# MCDU_Board.net
KiCad netlist of a schematic drawn in EAGLE
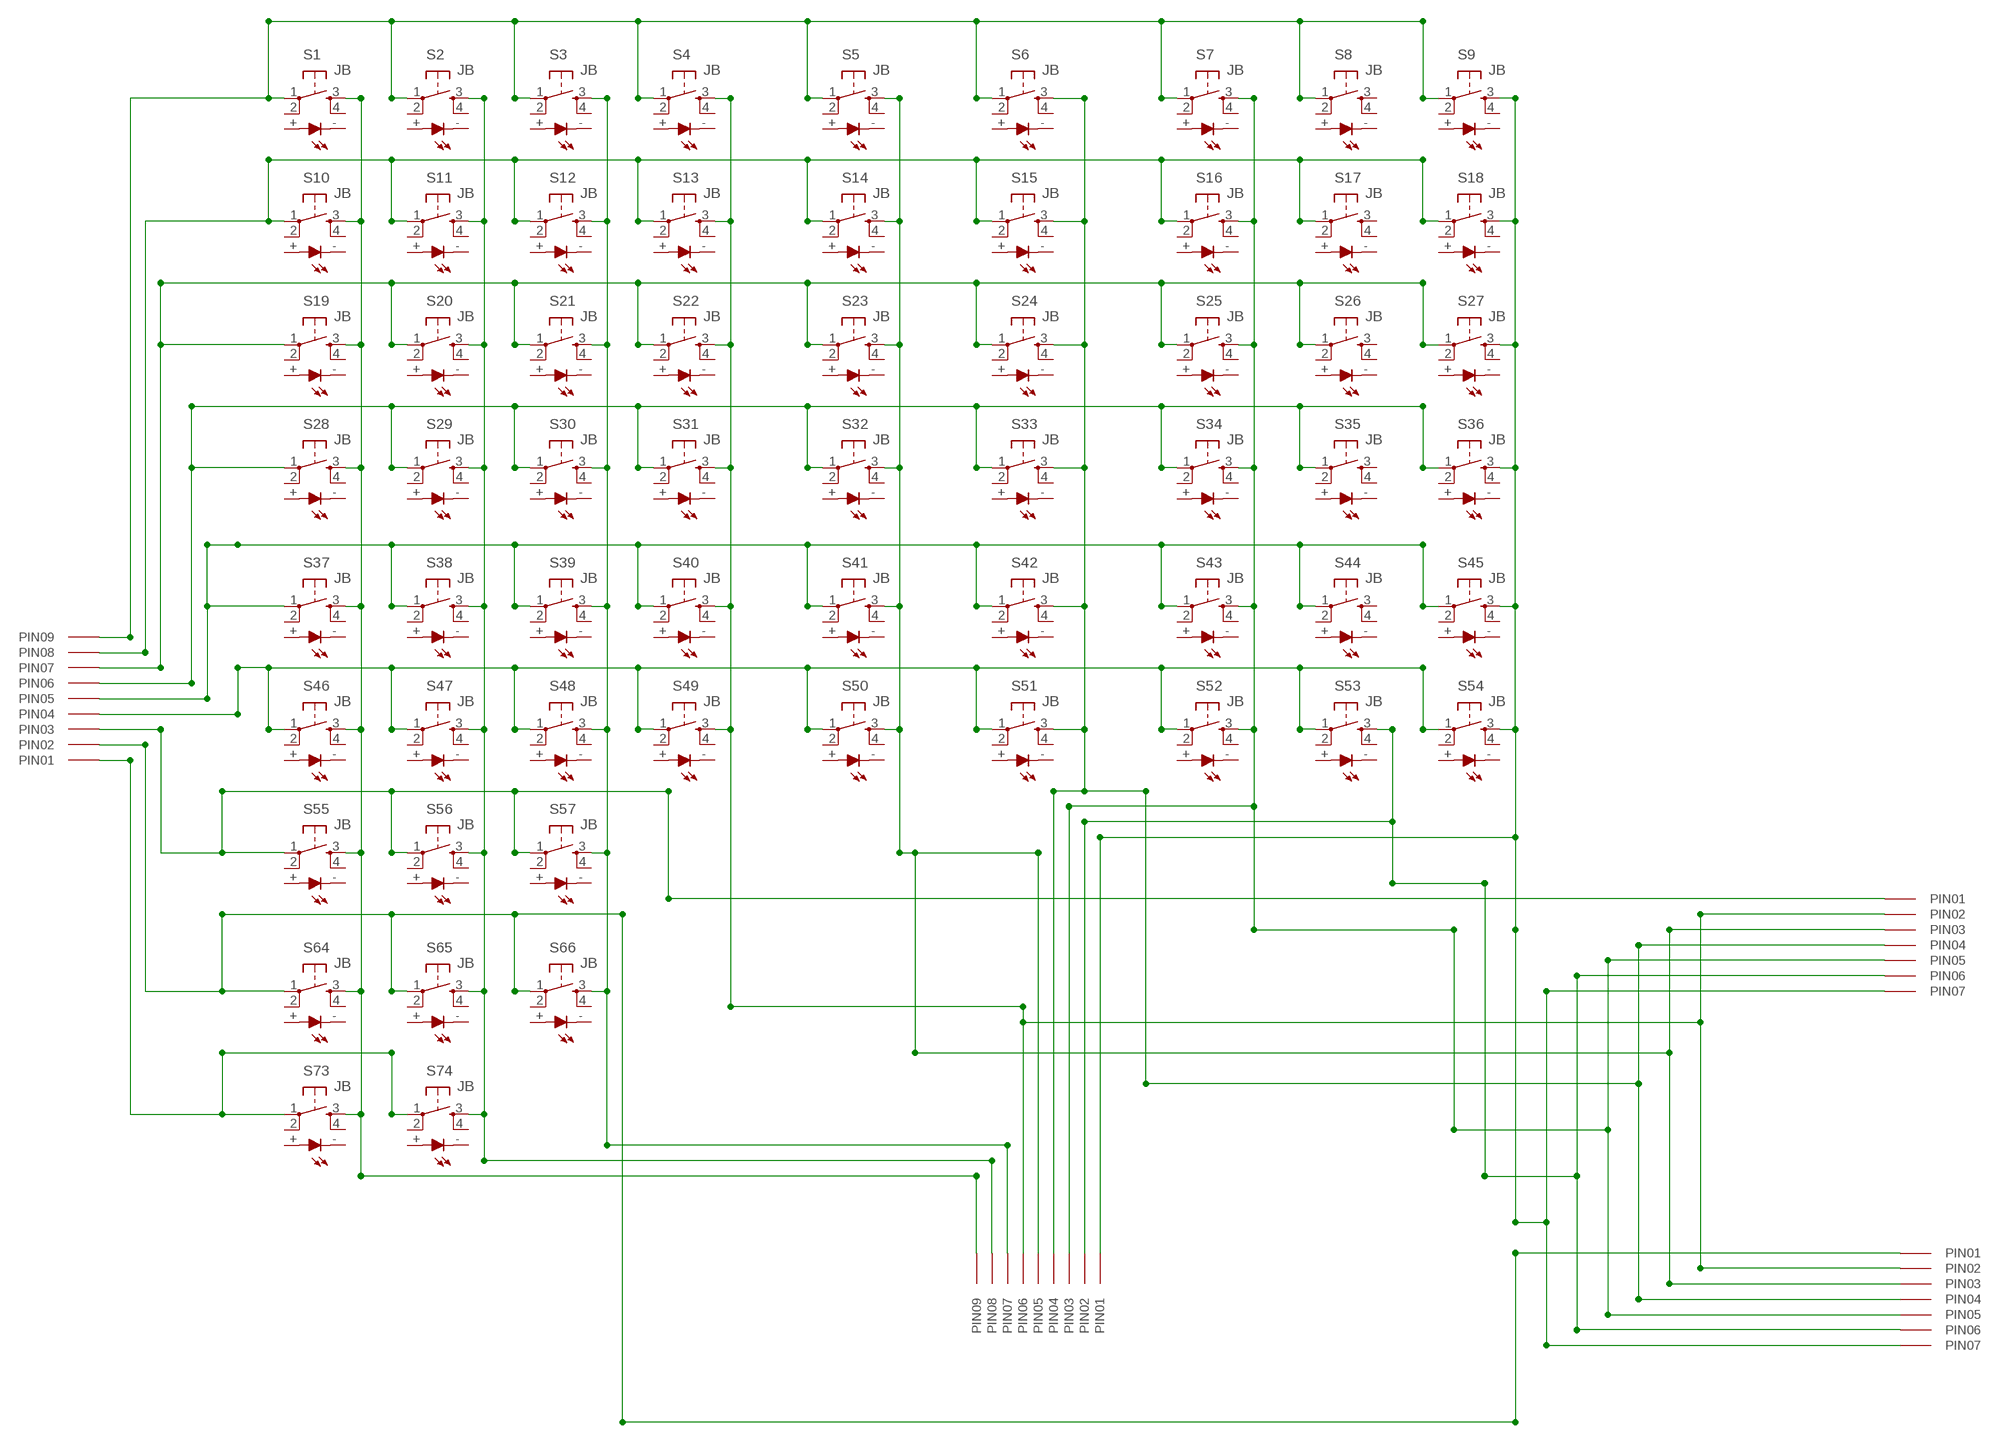
[diagram p0: schematic, sheet 1]

(export (version "E")
  (design (tool "Eeschema 10.0.6"))
  (components
    (comp (ref "S1") (value "JB") (footprint "eagle-import:JB") (libsource (lib "eagle-import") (part "JB")))
    (comp (ref "S2") (value "JB") (footprint "eagle-import:JB") (libsource (lib "eagle-import") (part "JB")))
    (comp (ref "S3") (value "JB") (footprint "eagle-import:JB") (libsource (lib "eagle-import") (part "JB")))
    (comp (ref "S4") (value "JB") (footprint "eagle-import:JB") (libsource (lib "eagle-import") (part "JB")))
    (comp (ref "S5") (value "JB") (footprint "eagle-import:JB") (libsource (lib "eagle-import") (part "JB")))
    (comp (ref "S6") (value "JB") (footprint "eagle-import:JB") (libsource (lib "eagle-import") (part "JB")))
    (comp (ref "S7") (value "JB") (footprint "eagle-import:JB") (libsource (lib "eagle-import") (part "JB")))
    (comp (ref "S8") (value "JB") (footprint "eagle-import:JB") (libsource (lib "eagle-import") (part "JB")))
    (comp (ref "S9") (value "JB") (footprint "eagle-import:JB") (libsource (lib "eagle-import") (part "JB")))
    (comp (ref "S10") (value "JB") (footprint "eagle-import:JB") (libsource (lib "eagle-import") (part "JB")))
    (comp (ref "S11") (value "JB") (footprint "eagle-import:JB") (libsource (lib "eagle-import") (part "JB")))
    (comp (ref "S12") (value "JB") (footprint "eagle-import:JB") (libsource (lib "eagle-import") (part "JB")))
    (comp (ref "S13") (value "JB") (footprint "eagle-import:JB") (libsource (lib "eagle-import") (part "JB")))
    (comp (ref "S14") (value "JB") (footprint "eagle-import:JB") (libsource (lib "eagle-import") (part "JB")))
    (comp (ref "S15") (value "JB") (footprint "eagle-import:JB") (libsource (lib "eagle-import") (part "JB")))
    (comp (ref "S16") (value "JB") (footprint "eagle-import:JB") (libsource (lib "eagle-import") (part "JB")))
    (comp (ref "S17") (value "JB") (footprint "eagle-import:JB") (libsource (lib "eagle-import") (part "JB")))
    (comp (ref "S18") (value "JB") (footprint "eagle-import:JB") (libsource (lib "eagle-import") (part "JB")))
    (comp (ref "S19") (value "JB") (footprint "eagle-import:JB") (libsource (lib "eagle-import") (part "JB")))
    (comp (ref "S20") (value "JB") (footprint "eagle-import:JB") (libsource (lib "eagle-import") (part "JB")))
    (comp (ref "S21") (value "JB") (footprint "eagle-import:JB") (libsource (lib "eagle-import") (part "JB")))
    (comp (ref "S22") (value "JB") (footprint "eagle-import:JB") (libsource (lib "eagle-import") (part "JB")))
    (comp (ref "S23") (value "JB") (footprint "eagle-import:JB") (libsource (lib "eagle-import") (part "JB")))
    (comp (ref "S24") (value "JB") (footprint "eagle-import:JB") (libsource (lib "eagle-import") (part "JB")))
    (comp (ref "S25") (value "JB") (footprint "eagle-import:JB") (libsource (lib "eagle-import") (part "JB")))
    (comp (ref "S26") (value "JB") (footprint "eagle-import:JB") (libsource (lib "eagle-import") (part "JB")))
    (comp (ref "S27") (value "JB") (footprint "eagle-import:JB") (libsource (lib "eagle-import") (part "JB")))
    (comp (ref "S28") (value "JB") (footprint "eagle-import:JB") (libsource (lib "eagle-import") (part "JB")))
    (comp (ref "S29") (value "JB") (footprint "eagle-import:JB") (libsource (lib "eagle-import") (part "JB")))
    (comp (ref "S30") (value "JB") (footprint "eagle-import:JB") (libsource (lib "eagle-import") (part "JB")))
    (comp (ref "S31") (value "JB") (footprint "eagle-import:JB") (libsource (lib "eagle-import") (part "JB")))
    (comp (ref "S32") (value "JB") (footprint "eagle-import:JB") (libsource (lib "eagle-import") (part "JB")))
    (comp (ref "S33") (value "JB") (footprint "eagle-import:JB") (libsource (lib "eagle-import") (part "JB")))
    (comp (ref "S34") (value "JB") (footprint "eagle-import:JB") (libsource (lib "eagle-import") (part "JB")))
    (comp (ref "S35") (value "JB") (footprint "eagle-import:JB") (libsource (lib "eagle-import") (part "JB")))
    (comp (ref "S36") (value "JB") (footprint "eagle-import:JB") (libsource (lib "eagle-import") (part "JB")))
    (comp (ref "S37") (value "JB") (footprint "eagle-import:JB") (libsource (lib "eagle-import") (part "JB")))
    (comp (ref "S38") (value "JB") (footprint "eagle-import:JB") (libsource (lib "eagle-import") (part "JB")))
    (comp (ref "S39") (value "JB") (footprint "eagle-import:JB") (libsource (lib "eagle-import") (part "JB")))
    (comp (ref "S40") (value "JB") (footprint "eagle-import:JB") (libsource (lib "eagle-import") (part "JB")))
    (comp (ref "S41") (value "JB") (footprint "eagle-import:JB") (libsource (lib "eagle-import") (part "JB")))
    (comp (ref "S42") (value "JB") (footprint "eagle-import:JB") (libsource (lib "eagle-import") (part "JB")))
    (comp (ref "S43") (value "JB") (footprint "eagle-import:JB") (libsource (lib "eagle-import") (part "JB")))
    (comp (ref "S44") (value "JB") (footprint "eagle-import:JB") (libsource (lib "eagle-import") (part "JB")))
    (comp (ref "S45") (value "JB") (footprint "eagle-import:JB") (libsource (lib "eagle-import") (part "JB")))
    (comp (ref "S46") (value "JB") (footprint "eagle-import:JB") (libsource (lib "eagle-import") (part "JB")))
    (comp (ref "S47") (value "JB") (footprint "eagle-import:JB") (libsource (lib "eagle-import") (part "JB")))
    (comp (ref "S48") (value "JB") (footprint "eagle-import:JB") (libsource (lib "eagle-import") (part "JB")))
    (comp (ref "S49") (value "JB") (footprint "eagle-import:JB") (libsource (lib "eagle-import") (part "JB")))
    (comp (ref "S50") (value "JB") (footprint "eagle-import:JB") (libsource (lib "eagle-import") (part "JB")))
    (comp (ref "S51") (value "JB") (footprint "eagle-import:JB") (libsource (lib "eagle-import") (part "JB")))
    (comp (ref "S52") (value "JB") (footprint "eagle-import:JB") (libsource (lib "eagle-import") (part "JB")))
    (comp (ref "S53") (value "JB") (footprint "eagle-import:JB") (libsource (lib "eagle-import") (part "JB")))
    (comp (ref "S54") (value "JB") (footprint "eagle-import:JB") (libsource (lib "eagle-import") (part "JB")))
    (comp (ref "S55") (value "JB") (footprint "eagle-import:JB") (libsource (lib "eagle-import") (part "JB")))
    (comp (ref "S56") (value "JB") (footprint "eagle-import:JB") (libsource (lib "eagle-import") (part "JB")))
    (comp (ref "S57") (value "JB") (footprint "eagle-import:JB") (libsource (lib "eagle-import") (part "JB")))
    (comp (ref "S64") (value "JB") (footprint "eagle-import:JB") (libsource (lib "eagle-import") (part "JB")))
    (comp (ref "S65") (value "JB") (footprint "eagle-import:JB") (libsource (lib "eagle-import") (part "JB")))
    (comp (ref "S66") (value "JB") (footprint "eagle-import:JB") (libsource (lib "eagle-import") (part "JB")))
    (comp (ref "S73") (value "JB") (footprint "eagle-import:JB") (libsource (lib "eagle-import") (part "JB")))
    (comp (ref "S74") (value "JB") (footprint "eagle-import:JB") (libsource (lib "eagle-import") (part "JB")))
    (comp (ref "U$1")
      (value "09PINOS")
      (footprint "eagle-import:09PINOS")
      (libsource (lib "eagle-import") (part "09PINOS"))
    )
    (comp (ref "U$2")
      (value "07PINOS")
      (footprint "eagle-import:07PINOS")
      (libsource (lib "eagle-import") (part "07PINOS"))
    )
    (comp (ref "U$3")
      (value "07PINOS")
      (footprint "eagle-import:07PINOS")
      (libsource (lib "eagle-import") (part "07PINOS"))
    )
    (comp (ref "U$4")
      (value "09PINOS")
      (footprint "eagle-import:09PINOS")
      (libsource (lib "eagle-import") (part "09PINOS"))
    )
  )
  (nets
    (net (code "1") (name "Net-(S1-P)") (class "Default")
      (node (ref "S1") (pin "1") (pinfunction "P_1") (pintype "passive"))
      (node (ref "S2") (pin "1") (pinfunction "P_1") (pintype "passive"))
      (node (ref "S3") (pin "1") (pinfunction "P_1") (pintype "passive"))
      (node (ref "S4") (pin "1") (pinfunction "P_1") (pintype "passive"))
      (node (ref "S5") (pin "1") (pinfunction "P_1") (pintype "passive"))
      (node (ref "S6") (pin "1") (pinfunction "P_1") (pintype "passive"))
      (node (ref "S7") (pin "1") (pinfunction "P_1") (pintype "passive"))
      (node (ref "S8") (pin "1") (pinfunction "P_1") (pintype "passive"))
      (node (ref "S9") (pin "1") (pinfunction "P_1") (pintype "passive"))
      (node (ref "U$1") (pin "PIN09") (pinfunction "PIN09_PIN09") (pintype "bidirectional"))
    )
    (net (code "2") (name "Net-(S1-S)") (class "Default")
      (node (ref "S1") (pin "3") (pinfunction "S_3") (pintype "passive"))
      (node (ref "S10") (pin "3") (pinfunction "S_3") (pintype "passive"))
      (node (ref "S19") (pin "3") (pinfunction "S_3") (pintype "passive"))
      (node (ref "S28") (pin "3") (pinfunction "S_3") (pintype "passive"))
      (node (ref "S37") (pin "3") (pinfunction "S_3") (pintype "passive"))
      (node (ref "S46") (pin "3") (pinfunction "S_3") (pintype "passive"))
      (node (ref "S55") (pin "3") (pinfunction "S_3") (pintype "passive"))
      (node (ref "S64") (pin "3") (pinfunction "S_3") (pintype "passive"))
      (node (ref "S73") (pin "3") (pinfunction "S_3") (pintype "passive"))
      (node (ref "U$4") (pin "PIN09") (pinfunction "PIN09_PIN09") (pintype "bidirectional"))
    )
    (net (code "3") (name "Net-(S10-P)") (class "Default")
      (node (ref "S10") (pin "1") (pinfunction "P_1") (pintype "passive"))
      (node (ref "S11") (pin "1") (pinfunction "P_1") (pintype "passive"))
      (node (ref "S12") (pin "1") (pinfunction "P_1") (pintype "passive"))
      (node (ref "S13") (pin "1") (pinfunction "P_1") (pintype "passive"))
      (node (ref "S14") (pin "1") (pinfunction "P_1") (pintype "passive"))
      (node (ref "S15") (pin "1") (pinfunction "P_1") (pintype "passive"))
      (node (ref "S16") (pin "1") (pinfunction "P_1") (pintype "passive"))
      (node (ref "S17") (pin "1") (pinfunction "P_1") (pintype "passive"))
      (node (ref "S18") (pin "1") (pinfunction "P_1") (pintype "passive"))
      (node (ref "U$1") (pin "PIN08") (pinfunction "PIN08_PIN08") (pintype "bidirectional"))
    )
    (net (code "4") (name "Net-(S11-S)") (class "Default")
      (node (ref "S11") (pin "3") (pinfunction "S_3") (pintype "passive"))
      (node (ref "S2") (pin "3") (pinfunction "S_3") (pintype "passive"))
      (node (ref "S20") (pin "3") (pinfunction "S_3") (pintype "passive"))
      (node (ref "S29") (pin "3") (pinfunction "S_3") (pintype "passive"))
      (node (ref "S38") (pin "3") (pinfunction "S_3") (pintype "passive"))
      (node (ref "S47") (pin "3") (pinfunction "S_3") (pintype "passive"))
      (node (ref "S56") (pin "3") (pinfunction "S_3") (pintype "passive"))
      (node (ref "S65") (pin "3") (pinfunction "S_3") (pintype "passive"))
      (node (ref "S74") (pin "3") (pinfunction "S_3") (pintype "passive"))
      (node (ref "U$4") (pin "PIN08") (pinfunction "PIN08_PIN08") (pintype "bidirectional"))
    )
    (net (code "5") (name "Net-(S12-S)") (class "Default")
      (node (ref "S12") (pin "3") (pinfunction "S_3") (pintype "passive"))
      (node (ref "S21") (pin "3") (pinfunction "S_3") (pintype "passive"))
      (node (ref "S3") (pin "3") (pinfunction "S_3") (pintype "passive"))
      (node (ref "S30") (pin "3") (pinfunction "S_3") (pintype "passive"))
      (node (ref "S39") (pin "3") (pinfunction "S_3") (pintype "passive"))
      (node (ref "S48") (pin "3") (pinfunction "S_3") (pintype "passive"))
      (node (ref "S57") (pin "3") (pinfunction "S_3") (pintype "passive"))
      (node (ref "S66") (pin "3") (pinfunction "S_3") (pintype "passive"))
      (node (ref "U$4") (pin "PIN07") (pinfunction "PIN07_PIN07") (pintype "bidirectional"))
    )
    (net (code "6") (name "Net-(S13-S)") (class "Default")
      (node (ref "S13") (pin "3") (pinfunction "S_3") (pintype "passive"))
      (node (ref "S22") (pin "3") (pinfunction "S_3") (pintype "passive"))
      (node (ref "S31") (pin "3") (pinfunction "S_3") (pintype "passive"))
      (node (ref "S4") (pin "3") (pinfunction "S_3") (pintype "passive"))
      (node (ref "S40") (pin "3") (pinfunction "S_3") (pintype "passive"))
      (node (ref "S49") (pin "3") (pinfunction "S_3") (pintype "passive"))
      (node (ref "U$2") (pin "PIN02") (pinfunction "PIN02_PIN02") (pintype "bidirectional"))
      (node (ref "U$3") (pin "PIN02") (pinfunction "PIN02_PIN02") (pintype "bidirectional"))
      (node (ref "U$4") (pin "PIN06") (pinfunction "PIN06_PIN06") (pintype "bidirectional"))
    )
    (net (code "7") (name "Net-(S14-S)") (class "Default")
      (node (ref "S14") (pin "3") (pinfunction "S_3") (pintype "passive"))
      (node (ref "S23") (pin "3") (pinfunction "S_3") (pintype "passive"))
      (node (ref "S32") (pin "3") (pinfunction "S_3") (pintype "passive"))
      (node (ref "S41") (pin "3") (pinfunction "S_3") (pintype "passive"))
      (node (ref "S5") (pin "3") (pinfunction "S_3") (pintype "passive"))
      (node (ref "S50") (pin "3") (pinfunction "S_3") (pintype "passive"))
      (node (ref "U$2") (pin "PIN03") (pinfunction "PIN03_PIN03") (pintype "bidirectional"))
      (node (ref "U$3") (pin "PIN03") (pinfunction "PIN03_PIN03") (pintype "bidirectional"))
      (node (ref "U$4") (pin "PIN05") (pinfunction "PIN05_PIN05") (pintype "bidirectional"))
    )
    (net (code "8") (name "Net-(S15-S)") (class "Default")
      (node (ref "S15") (pin "3") (pinfunction "S_3") (pintype "passive"))
      (node (ref "S24") (pin "3") (pinfunction "S_3") (pintype "passive"))
      (node (ref "S33") (pin "3") (pinfunction "S_3") (pintype "passive"))
      (node (ref "S42") (pin "3") (pinfunction "S_3") (pintype "passive"))
      (node (ref "S51") (pin "3") (pinfunction "S_3") (pintype "passive"))
      (node (ref "S6") (pin "3") (pinfunction "S_3") (pintype "passive"))
      (node (ref "U$2") (pin "PIN04") (pinfunction "PIN04_PIN04") (pintype "bidirectional"))
      (node (ref "U$3") (pin "PIN04") (pinfunction "PIN04_PIN04") (pintype "bidirectional"))
      (node (ref "U$4") (pin "PIN04") (pinfunction "PIN04_PIN04") (pintype "bidirectional"))
    )
    (net (code "9") (name "Net-(S16-S)") (class "Default")
      (node (ref "S16") (pin "3") (pinfunction "S_3") (pintype "passive"))
      (node (ref "S25") (pin "3") (pinfunction "S_3") (pintype "passive"))
      (node (ref "S34") (pin "3") (pinfunction "S_3") (pintype "passive"))
      (node (ref "S43") (pin "3") (pinfunction "S_3") (pintype "passive"))
      (node (ref "S52") (pin "3") (pinfunction "S_3") (pintype "passive"))
      (node (ref "S7") (pin "3") (pinfunction "S_3") (pintype "passive"))
      (node (ref "U$2") (pin "PIN05") (pinfunction "PIN05_PIN05") (pintype "bidirectional"))
      (node (ref "U$3") (pin "PIN05") (pinfunction "PIN05_PIN05") (pintype "bidirectional"))
      (node (ref "U$4") (pin "PIN03") (pinfunction "PIN03_PIN03") (pintype "bidirectional"))
    )
    (net (code "10") (name "Net-(S18-S)") (class "Default")
      (node (ref "S18") (pin "3") (pinfunction "S_3") (pintype "passive"))
      (node (ref "S27") (pin "3") (pinfunction "S_3") (pintype "passive"))
      (node (ref "S36") (pin "3") (pinfunction "S_3") (pintype "passive"))
      (node (ref "S45") (pin "3") (pinfunction "S_3") (pintype "passive"))
      (node (ref "S54") (pin "3") (pinfunction "S_3") (pintype "passive"))
      (node (ref "S9") (pin "3") (pinfunction "S_3") (pintype "passive"))
      (node (ref "U$2") (pin "PIN07") (pinfunction "PIN07_PIN07") (pintype "bidirectional"))
      (node (ref "U$3") (pin "PIN07") (pinfunction "PIN07_PIN07") (pintype "bidirectional"))
      (node (ref "U$4") (pin "PIN01") (pinfunction "PIN01_PIN01") (pintype "bidirectional"))
    )
    (net (code "11") (name "Net-(S19-P)") (class "Default")
      (node (ref "S19") (pin "1") (pinfunction "P_1") (pintype "passive"))
      (node (ref "S20") (pin "1") (pinfunction "P_1") (pintype "passive"))
      (node (ref "S21") (pin "1") (pinfunction "P_1") (pintype "passive"))
      (node (ref "S22") (pin "1") (pinfunction "P_1") (pintype "passive"))
      (node (ref "S23") (pin "1") (pinfunction "P_1") (pintype "passive"))
      (node (ref "S24") (pin "1") (pinfunction "P_1") (pintype "passive"))
      (node (ref "S25") (pin "1") (pinfunction "P_1") (pintype "passive"))
      (node (ref "S26") (pin "1") (pinfunction "P_1") (pintype "passive"))
      (node (ref "S27") (pin "1") (pinfunction "P_1") (pintype "passive"))
      (node (ref "U$1") (pin "PIN07") (pinfunction "PIN07_PIN07") (pintype "bidirectional"))
    )
    (net (code "12") (name "Net-(S28-P)") (class "Default")
      (node (ref "S28") (pin "1") (pinfunction "P_1") (pintype "passive"))
      (node (ref "S29") (pin "1") (pinfunction "P_1") (pintype "passive"))
      (node (ref "S30") (pin "1") (pinfunction "P_1") (pintype "passive"))
      (node (ref "S31") (pin "1") (pinfunction "P_1") (pintype "passive"))
      (node (ref "S32") (pin "1") (pinfunction "P_1") (pintype "passive"))
      (node (ref "S33") (pin "1") (pinfunction "P_1") (pintype "passive"))
      (node (ref "S34") (pin "1") (pinfunction "P_1") (pintype "passive"))
      (node (ref "S35") (pin "1") (pinfunction "P_1") (pintype "passive"))
      (node (ref "S36") (pin "1") (pinfunction "P_1") (pintype "passive"))
      (node (ref "U$1") (pin "PIN06") (pinfunction "PIN06_PIN06") (pintype "bidirectional"))
    )
    (net (code "13") (name "Net-(S37-P)") (class "Default")
      (node (ref "S37") (pin "1") (pinfunction "P_1") (pintype "passive"))
      (node (ref "S38") (pin "1") (pinfunction "P_1") (pintype "passive"))
      (node (ref "S39") (pin "1") (pinfunction "P_1") (pintype "passive"))
      (node (ref "S40") (pin "1") (pinfunction "P_1") (pintype "passive"))
      (node (ref "S41") (pin "1") (pinfunction "P_1") (pintype "passive"))
      (node (ref "S42") (pin "1") (pinfunction "P_1") (pintype "passive"))
      (node (ref "S43") (pin "1") (pinfunction "P_1") (pintype "passive"))
      (node (ref "S44") (pin "1") (pinfunction "P_1") (pintype "passive"))
      (node (ref "S45") (pin "1") (pinfunction "P_1") (pintype "passive"))
      (node (ref "U$1") (pin "PIN05") (pinfunction "PIN05_PIN05") (pintype "bidirectional"))
    )
    (net (code "14") (name "Net-(S46-P)") (class "Default")
      (node (ref "S46") (pin "1") (pinfunction "P_1") (pintype "passive"))
      (node (ref "S47") (pin "1") (pinfunction "P_1") (pintype "passive"))
      (node (ref "S48") (pin "1") (pinfunction "P_1") (pintype "passive"))
      (node (ref "S49") (pin "1") (pinfunction "P_1") (pintype "passive"))
      (node (ref "S50") (pin "1") (pinfunction "P_1") (pintype "passive"))
      (node (ref "S51") (pin "1") (pinfunction "P_1") (pintype "passive"))
      (node (ref "S52") (pin "1") (pinfunction "P_1") (pintype "passive"))
      (node (ref "S53") (pin "1") (pinfunction "P_1") (pintype "passive"))
      (node (ref "S54") (pin "1") (pinfunction "P_1") (pintype "passive"))
      (node (ref "U$1") (pin "PIN04") (pinfunction "PIN04_PIN04") (pintype "bidirectional"))
    )
    (net (code "15") (name "Net-(S53-S)") (class "Default")
      (node (ref "S53") (pin "3") (pinfunction "S_3") (pintype "passive"))
      (node (ref "U$2") (pin "PIN06") (pinfunction "PIN06_PIN06") (pintype "bidirectional"))
      (node (ref "U$3") (pin "PIN06") (pinfunction "PIN06_PIN06") (pintype "bidirectional"))
      (node (ref "U$4") (pin "PIN02") (pinfunction "PIN02_PIN02") (pintype "bidirectional"))
    )
    (net (code "16") (name "Net-(S55-P)") (class "Default")
      (node (ref "S55") (pin "1") (pinfunction "P_1") (pintype "passive"))
      (node (ref "S56") (pin "1") (pinfunction "P_1") (pintype "passive"))
      (node (ref "S57") (pin "1") (pinfunction "P_1") (pintype "passive"))
      (node (ref "U$1") (pin "PIN03") (pinfunction "PIN03_PIN03") (pintype "bidirectional"))
      (node (ref "U$2") (pin "PIN01") (pinfunction "PIN01_PIN01") (pintype "bidirectional"))
    )
    (net (code "17") (name "Net-(S64-P)") (class "Default")
      (node (ref "S64") (pin "1") (pinfunction "P_1") (pintype "passive"))
      (node (ref "S65") (pin "1") (pinfunction "P_1") (pintype "passive"))
      (node (ref "S66") (pin "1") (pinfunction "P_1") (pintype "passive"))
      (node (ref "U$1") (pin "PIN02") (pinfunction "PIN02_PIN02") (pintype "bidirectional"))
      (node (ref "U$3") (pin "PIN01") (pinfunction "PIN01_PIN01") (pintype "bidirectional"))
    )
    (net (code "18") (name "Net-(S73-P)") (class "Default")
      (node (ref "S73") (pin "1") (pinfunction "P_1") (pintype "passive"))
      (node (ref "S74") (pin "1") (pinfunction "P_1") (pintype "passive"))
      (node (ref "U$1") (pin "PIN01") (pinfunction "PIN01_PIN01") (pintype "bidirectional"))
    )
    (net (code "19") (name "unconnected-(S1-A-Pad+)") (class "Default")
      (node (ref "S1") (pin "+") (pinfunction "A_+") (pintype "passive"))
    )
    (net (code "20") (name "unconnected-(S1-C-Pad-)") (class "Default")
      (node (ref "S1") (pin "-") (pinfunction "C_-") (pintype "passive"))
    )
    (net (code "21") (name "unconnected-(S1-P1-Pad2)") (class "Default")
      (node (ref "S1") (pin "2") (pinfunction "P1_2") (pintype "passive"))
    )
    (net (code "22") (name "unconnected-(S1-S1-Pad4)") (class "Default")
      (node (ref "S1") (pin "4") (pinfunction "S1_4") (pintype "passive"))
    )
    (net (code "23") (name "unconnected-(S2-A-Pad+)") (class "Default")
      (node (ref "S2") (pin "+") (pinfunction "A_+") (pintype "passive"))
    )
    (net (code "24") (name "unconnected-(S2-C-Pad-)") (class "Default")
      (node (ref "S2") (pin "-") (pinfunction "C_-") (pintype "passive"))
    )
    (net (code "25") (name "unconnected-(S2-P1-Pad2)") (class "Default")
      (node (ref "S2") (pin "2") (pinfunction "P1_2") (pintype "passive"))
    )
    (net (code "26") (name "unconnected-(S2-S1-Pad4)") (class "Default")
      (node (ref "S2") (pin "4") (pinfunction "S1_4") (pintype "passive"))
    )
    (net (code "27") (name "unconnected-(S3-A-Pad+)") (class "Default")
      (node (ref "S3") (pin "+") (pinfunction "A_+") (pintype "passive"))
    )
    (net (code "28") (name "unconnected-(S3-C-Pad-)") (class "Default")
      (node (ref "S3") (pin "-") (pinfunction "C_-") (pintype "passive"))
    )
    (net (code "29") (name "unconnected-(S3-P1-Pad2)") (class "Default")
      (node (ref "S3") (pin "2") (pinfunction "P1_2") (pintype "passive"))
    )
    (net (code "30") (name "unconnected-(S3-S1-Pad4)") (class "Default")
      (node (ref "S3") (pin "4") (pinfunction "S1_4") (pintype "passive"))
    )
    (net (code "31") (name "unconnected-(S4-A-Pad+)") (class "Default")
      (node (ref "S4") (pin "+") (pinfunction "A_+") (pintype "passive"))
    )
    (net (code "32") (name "unconnected-(S4-C-Pad-)") (class "Default")
      (node (ref "S4") (pin "-") (pinfunction "C_-") (pintype "passive"))
    )
    (net (code "33") (name "unconnected-(S4-P1-Pad2)") (class "Default")
      (node (ref "S4") (pin "2") (pinfunction "P1_2") (pintype "passive"))
    )
    (net (code "34") (name "unconnected-(S4-S1-Pad4)") (class "Default")
      (node (ref "S4") (pin "4") (pinfunction "S1_4") (pintype "passive"))
    )
    (net (code "35") (name "unconnected-(S5-A-Pad+)") (class "Default")
      (node (ref "S5") (pin "+") (pinfunction "A_+") (pintype "passive"))
    )
    (net (code "36") (name "unconnected-(S5-C-Pad-)") (class "Default")
      (node (ref "S5") (pin "-") (pinfunction "C_-") (pintype "passive"))
    )
    (net (code "37") (name "unconnected-(S5-P1-Pad2)") (class "Default")
      (node (ref "S5") (pin "2") (pinfunction "P1_2") (pintype "passive"))
    )
    (net (code "38") (name "unconnected-(S5-S1-Pad4)") (class "Default")
      (node (ref "S5") (pin "4") (pinfunction "S1_4") (pintype "passive"))
    )
    (net (code "39") (name "unconnected-(S6-A-Pad+)") (class "Default")
      (node (ref "S6") (pin "+") (pinfunction "A_+") (pintype "passive"))
    )
    (net (code "40") (name "unconnected-(S6-C-Pad-)") (class "Default")
      (node (ref "S6") (pin "-") (pinfunction "C_-") (pintype "passive"))
    )
    (net (code "41") (name "unconnected-(S6-P1-Pad2)") (class "Default")
      (node (ref "S6") (pin "2") (pinfunction "P1_2") (pintype "passive"))
    )
    (net (code "42") (name "unconnected-(S6-S1-Pad4)") (class "Default")
      (node (ref "S6") (pin "4") (pinfunction "S1_4") (pintype "passive"))
    )
    (net (code "43") (name "unconnected-(S7-A-Pad+)") (class "Default")
      (node (ref "S7") (pin "+") (pinfunction "A_+") (pintype "passive"))
    )
    (net (code "44") (name "unconnected-(S7-C-Pad-)") (class "Default")
      (node (ref "S7") (pin "-") (pinfunction "C_-") (pintype "passive"))
    )
    (net (code "45") (name "unconnected-(S7-P1-Pad2)") (class "Default")
      (node (ref "S7") (pin "2") (pinfunction "P1_2") (pintype "passive"))
    )
    (net (code "46") (name "unconnected-(S7-S1-Pad4)") (class "Default")
      (node (ref "S7") (pin "4") (pinfunction "S1_4") (pintype "passive"))
    )
    (net (code "47") (name "unconnected-(S8-A-Pad+)") (class "Default")
      (node (ref "S8") (pin "+") (pinfunction "A_+") (pintype "passive"))
    )
    (net (code "48") (name "unconnected-(S8-C-Pad-)") (class "Default")
      (node (ref "S8") (pin "-") (pinfunction "C_-") (pintype "passive"))
    )
    (net (code "49") (name "unconnected-(S8-P1-Pad2)") (class "Default")
      (node (ref "S8") (pin "2") (pinfunction "P1_2") (pintype "passive"))
    )
    (net (code "50") (name "unconnected-(S8-S-Pad3)") (class "Default")
      (node (ref "S8") (pin "3") (pinfunction "S_3") (pintype "passive"))
    )
    (net (code "51") (name "unconnected-(S8-S1-Pad4)") (class "Default")
      (node (ref "S8") (pin "4") (pinfunction "S1_4") (pintype "passive"))
    )
    (net (code "52") (name "unconnected-(S9-A-Pad+)") (class "Default")
      (node (ref "S9") (pin "+") (pinfunction "A_+") (pintype "passive"))
    )
    (net (code "53") (name "unconnected-(S9-C-Pad-)") (class "Default")
      (node (ref "S9") (pin "-") (pinfunction "C_-") (pintype "passive"))
    )
    (net (code "54") (name "unconnected-(S9-P1-Pad2)") (class "Default")
      (node (ref "S9") (pin "2") (pinfunction "P1_2") (pintype "passive"))
    )
    (net (code "55") (name "unconnected-(S9-S1-Pad4)") (class "Default")
      (node (ref "S9") (pin "4") (pinfunction "S1_4") (pintype "passive"))
    )
    (net (code "56") (name "unconnected-(S10-A-Pad+)") (class "Default")
      (node (ref "S10") (pin "+") (pinfunction "A_+") (pintype "passive"))
    )
    (net (code "57") (name "unconnected-(S10-C-Pad-)") (class "Default")
      (node (ref "S10") (pin "-") (pinfunction "C_-") (pintype "passive"))
    )
    (net (code "58") (name "unconnected-(S10-P1-Pad2)") (class "Default")
      (node (ref "S10") (pin "2") (pinfunction "P1_2") (pintype "passive"))
    )
    (net (code "59") (name "unconnected-(S10-S1-Pad4)") (class "Default")
      (node (ref "S10") (pin "4") (pinfunction "S1_4") (pintype "passive"))
    )
    (net (code "60") (name "unconnected-(S11-A-Pad+)") (class "Default")
      (node (ref "S11") (pin "+") (pinfunction "A_+") (pintype "passive"))
    )
    (net (code "61") (name "unconnected-(S11-C-Pad-)") (class "Default")
      (node (ref "S11") (pin "-") (pinfunction "C_-") (pintype "passive"))
    )
    (net (code "62") (name "unconnected-(S11-P1-Pad2)") (class "Default")
      (node (ref "S11") (pin "2") (pinfunction "P1_2") (pintype "passive"))
    )
    (net (code "63") (name "unconnected-(S11-S1-Pad4)") (class "Default")
      (node (ref "S11") (pin "4") (pinfunction "S1_4") (pintype "passive"))
    )
    (net (code "64") (name "unconnected-(S12-A-Pad+)") (class "Default")
      (node (ref "S12") (pin "+") (pinfunction "A_+") (pintype "passive"))
    )
    (net (code "65") (name "unconnected-(S12-C-Pad-)") (class "Default")
      (node (ref "S12") (pin "-") (pinfunction "C_-") (pintype "passive"))
    )
    (net (code "66") (name "unconnected-(S12-P1-Pad2)") (class "Default")
      (node (ref "S12") (pin "2") (pinfunction "P1_2") (pintype "passive"))
    )
    (net (code "67") (name "unconnected-(S12-S1-Pad4)") (class "Default")
      (node (ref "S12") (pin "4") (pinfunction "S1_4") (pintype "passive"))
    )
    (net (code "68") (name "unconnected-(S13-A-Pad+)") (class "Default")
      (node (ref "S13") (pin "+") (pinfunction "A_+") (pintype "passive"))
    )
    (net (code "69") (name "unconnected-(S13-C-Pad-)") (class "Default")
      (node (ref "S13") (pin "-") (pinfunction "C_-") (pintype "passive"))
    )
    (net (code "70") (name "unconnected-(S13-P1-Pad2)") (class "Default")
      (node (ref "S13") (pin "2") (pinfunction "P1_2") (pintype "passive"))
    )
    (net (code "71") (name "unconnected-(S13-S1-Pad4)") (class "Default")
      (node (ref "S13") (pin "4") (pinfunction "S1_4") (pintype "passive"))
    )
    (net (code "72") (name "unconnected-(S14-A-Pad+)") (class "Default")
      (node (ref "S14") (pin "+") (pinfunction "A_+") (pintype "passive"))
    )
    (net (code "73") (name "unconnected-(S14-C-Pad-)") (class "Default")
      (node (ref "S14") (pin "-") (pinfunction "C_-") (pintype "passive"))
    )
    (net (code "74") (name "unconnected-(S14-P1-Pad2)") (class "Default")
      (node (ref "S14") (pin "2") (pinfunction "P1_2") (pintype "passive"))
    )
    (net (code "75") (name "unconnected-(S14-S1-Pad4)") (class "Default")
      (node (ref "S14") (pin "4") (pinfunction "S1_4") (pintype "passive"))
    )
    (net (code "76") (name "unconnected-(S15-A-Pad+)") (class "Default")
      (node (ref "S15") (pin "+") (pinfunction "A_+") (pintype "passive"))
    )
    (net (code "77") (name "unconnected-(S15-C-Pad-)") (class "Default")
      (node (ref "S15") (pin "-") (pinfunction "C_-") (pintype "passive"))
    )
    (net (code "78") (name "unconnected-(S15-P1-Pad2)") (class "Default")
      (node (ref "S15") (pin "2") (pinfunction "P1_2") (pintype "passive"))
    )
    (net (code "79") (name "unconnected-(S15-S1-Pad4)") (class "Default")
      (node (ref "S15") (pin "4") (pinfunction "S1_4") (pintype "passive"))
    )
    (net (code "80") (name "unconnected-(S16-A-Pad+)") (class "Default")
      (node (ref "S16") (pin "+") (pinfunction "A_+") (pintype "passive"))
    )
    (net (code "81") (name "unconnected-(S16-C-Pad-)") (class "Default")
      (node (ref "S16") (pin "-") (pinfunction "C_-") (pintype "passive"))
    )
    (net (code "82") (name "unconnected-(S16-P1-Pad2)") (class "Default")
      (node (ref "S16") (pin "2") (pinfunction "P1_2") (pintype "passive"))
    )
    (net (code "83") (name "unconnected-(S16-S1-Pad4)") (class "Default")
      (node (ref "S16") (pin "4") (pinfunction "S1_4") (pintype "passive"))
    )
    (net (code "84") (name "unconnected-(S17-A-Pad+)") (class "Default")
      (node (ref "S17") (pin "+") (pinfunction "A_+") (pintype "passive"))
    )
    (net (code "85") (name "unconnected-(S17-C-Pad-)") (class "Default")
      (node (ref "S17") (pin "-") (pinfunction "C_-") (pintype "passive"))
    )
    (net (code "86") (name "unconnected-(S17-P1-Pad2)") (class "Default")
      (node (ref "S17") (pin "2") (pinfunction "P1_2") (pintype "passive"))
    )
    (net (code "87") (name "unconnected-(S17-S-Pad3)") (class "Default")
      (node (ref "S17") (pin "3") (pinfunction "S_3") (pintype "passive"))
    )
    (net (code "88") (name "unconnected-(S17-S1-Pad4)") (class "Default")
      (node (ref "S17") (pin "4") (pinfunction "S1_4") (pintype "passive"))
    )
    (net (code "89") (name "unconnected-(S18-A-Pad+)") (class "Default")
      (node (ref "S18") (pin "+") (pinfunction "A_+") (pintype "passive"))
    )
    (net (code "90") (name "unconnected-(S18-C-Pad-)") (class "Default")
      (node (ref "S18") (pin "-") (pinfunction "C_-") (pintype "passive"))
    )
    (net (code "91") (name "unconnected-(S18-P1-Pad2)") (class "Default")
      (node (ref "S18") (pin "2") (pinfunction "P1_2") (pintype "passive"))
    )
    (net (code "92") (name "unconnected-(S18-S1-Pad4)") (class "Default")
      (node (ref "S18") (pin "4") (pinfunction "S1_4") (pintype "passive"))
    )
    (net (code "93") (name "unconnected-(S19-A-Pad+)") (class "Default")
      (node (ref "S19") (pin "+") (pinfunction "A_+") (pintype "passive"))
    )
    (net (code "94") (name "unconnected-(S19-C-Pad-)") (class "Default")
      (node (ref "S19") (pin "-") (pinfunction "C_-") (pintype "passive"))
    )
    (net (code "95") (name "unconnected-(S19-P1-Pad2)") (class "Default")
      (node (ref "S19") (pin "2") (pinfunction "P1_2") (pintype "passive"))
    )
    (net (code "96") (name "unconnected-(S19-S1-Pad4)") (class "Default")
      (node (ref "S19") (pin "4") (pinfunction "S1_4") (pintype "passive"))
    )
    (net (code "97") (name "unconnected-(S20-A-Pad+)") (class "Default")
      (node (ref "S20") (pin "+") (pinfunction "A_+") (pintype "passive"))
    )
    (net (code "98") (name "unconnected-(S20-C-Pad-)") (class "Default")
      (node (ref "S20") (pin "-") (pinfunction "C_-") (pintype "passive"))
    )
    (net (code "99") (name "unconnected-(S20-P1-Pad2)") (class "Default")
      (node (ref "S20") (pin "2") (pinfunction "P1_2") (pintype "passive"))
    )
    (net (code "100") (name "unconnected-(S20-S1-Pad4)") (class "Default")
      (node (ref "S20") (pin "4") (pinfunction "S1_4") (pintype "passive"))
    )
    (net (code "101") (name "unconnected-(S21-A-Pad+)") (class "Default")
      (node (ref "S21") (pin "+") (pinfunction "A_+") (pintype "passive"))
    )
    (net (code "102") (name "unconnected-(S21-C-Pad-)") (class "Default")
      (node (ref "S21") (pin "-") (pinfunction "C_-") (pintype "passive"))
    )
    (net (code "103") (name "unconnected-(S21-P1-Pad2)") (class "Default")
      (node (ref "S21") (pin "2") (pinfunction "P1_2") (pintype "passive"))
    )
    (net (code "104") (name "unconnected-(S21-S1-Pad4)") (class "Default")
      (node (ref "S21") (pin "4") (pinfunction "S1_4") (pintype "passive"))
    )
    (net (code "105") (name "unconnected-(S22-A-Pad+)") (class "Default")
      (node (ref "S22") (pin "+") (pinfunction "A_+") (pintype "passive"))
    )
    (net (code "106") (name "unconnected-(S22-C-Pad-)") (class "Default")
      (node (ref "S22") (pin "-") (pinfunction "C_-") (pintype "passive"))
    )
    (net (code "107") (name "unconnected-(S22-P1-Pad2)") (class "Default")
      (node (ref "S22") (pin "2") (pinfunction "P1_2") (pintype "passive"))
    )
    (net (code "108") (name "unconnected-(S22-S1-Pad4)") (class "Default")
      (node (ref "S22") (pin "4") (pinfunction "S1_4") (pintype "passive"))
    )
    (net (code "109") (name "unconnected-(S23-A-Pad+)") (class "Default")
      (node (ref "S23") (pin "+") (pinfunction "A_+") (pintype "passive"))
    )
    (net (code "110") (name "unconnected-(S23-C-Pad-)") (class "Default")
      (node (ref "S23") (pin "-") (pinfunction "C_-") (pintype "passive"))
    )
    (net (code "111") (name "unconnected-(S23-P1-Pad2)") (class "Default")
      (node (ref "S23") (pin "2") (pinfunction "P1_2") (pintype "passive"))
    )
    (net (code "112") (name "unconnected-(S23-S1-Pad4)") (class "Default")
      (node (ref "S23") (pin "4") (pinfunction "S1_4") (pintype "passive"))
    )
    (net (code "113") (name "unconnected-(S24-A-Pad+)") (class "Default")
      (node (ref "S24") (pin "+") (pinfunction "A_+") (pintype "passive"))
    )
    (net (code "114") (name "unconnected-(S24-C-Pad-)") (class "Default")
      (node (ref "S24") (pin "-") (pinfunction "C_-") (pintype "passive"))
    )
    (net (code "115") (name "unconnected-(S24-P1-Pad2)") (class "Default")
      (node (ref "S24") (pin "2") (pinfunction "P1_2") (pintype "passive"))
    )
    (net (code "116") (name "unconnected-(S24-S1-Pad4)") (class "Default")
      (node (ref "S24") (pin "4") (pinfunction "S1_4") (pintype "passive"))
    )
    (net (code "117") (name "unconnected-(S25-A-Pad+)") (class "Default")
      (node (ref "S25") (pin "+") (pinfunction "A_+") (pintype "passive"))
    )
    (net (code "118") (name "unconnected-(S25-C-Pad-)") (class "Default")
      (node (ref "S25") (pin "-") (pinfunction "C_-") (pintype "passive"))
    )
    (net (code "119") (name "unconnected-(S25-P1-Pad2)") (class "Default")
      (node (ref "S25") (pin "2") (pinfunction "P1_2") (pintype "passive"))
    )
    (net (code "120") (name "unconnected-(S25-S1-Pad4)") (class "Default")
      (node (ref "S25") (pin "4") (pinfunction "S1_4") (pintype "passive"))
    )
    (net (code "121") (name "unconnected-(S26-A-Pad+)") (class "Default")
      (node (ref "S26") (pin "+") (pinfunction "A_+") (pintype "passive"))
    )
    (net (code "122") (name "unconnected-(S26-C-Pad-)") (class "Default")
      (node (ref "S26") (pin "-") (pinfunction "C_-") (pintype "passive"))
    )
    (net (code "123") (name "unconnected-(S26-P1-Pad2)") (class "Default")
      (node (ref "S26") (pin "2") (pinfunction "P1_2") (pintype "passive"))
    )
    (net (code "124") (name "unconnected-(S26-S-Pad3)") (class "Default")
      (node (ref "S26") (pin "3") (pinfunction "S_3") (pintype "passive"))
    )
    (net (code "125") (name "unconnected-(S26-S1-Pad4)") (class "Default")
      (node (ref "S26") (pin "4") (pinfunction "S1_4") (pintype "passive"))
    )
    (net (code "126") (name "unconnected-(S27-A-Pad+)") (class "Default")
      (node (ref "S27") (pin "+") (pinfunction "A_+") (pintype "passive"))
    )
    (net (code "127") (name "unconnected-(S27-C-Pad-)") (class "Default")
      (node (ref "S27") (pin "-") (pinfunction "C_-") (pintype "passive"))
    )
    (net (code "128") (name "unconnected-(S27-P1-Pad2)") (class "Default")
      (node (ref "S27") (pin "2") (pinfunction "P1_2") (pintype "passive"))
    )
    (net (code "129") (name "unconnected-(S27-S1-Pad4)") (class "Default")
      (node (ref "S27") (pin "4") (pinfunction "S1_4") (pintype "passive"))
    )
    (net (code "130") (name "unconnected-(S28-A-Pad+)") (class "Default")
      (node (ref "S28") (pin "+") (pinfunction "A_+") (pintype "passive"))
    )
    (net (code "131") (name "unconnected-(S28-C-Pad-)") (class "Default")
      (node (ref "S28") (pin "-") (pinfunction "C_-") (pintype "passive"))
    )
    (net (code "132") (name "unconnected-(S28-P1-Pad2)") (class "Default")
      (node (ref "S28") (pin "2") (pinfunction "P1_2") (pintype "passive"))
    )
    (net (code "133") (name "unconnected-(S28-S1-Pad4)") (class "Default")
      (node (ref "S28") (pin "4") (pinfunction "S1_4") (pintype "passive"))
    )
    (net (code "134") (name "unconnected-(S29-A-Pad+)") (class "Default")
      (node (ref "S29") (pin "+") (pinfunction "A_+") (pintype "passive"))
    )
    (net (code "135") (name "unconnected-(S29-C-Pad-)") (class "Default")
      (node (ref "S29") (pin "-") (pinfunction "C_-") (pintype "passive"))
    )
    (net (code "136") (name "unconnected-(S29-P1-Pad2)") (class "Default")
      (node (ref "S29") (pin "2") (pinfunction "P1_2") (pintype "passive"))
    )
    (net (code "137") (name "unconnected-(S29-S1-Pad4)") (class "Default")
      (node (ref "S29") (pin "4") (pinfunction "S1_4") (pintype "passive"))
    )
    (net (code "138") (name "unconnected-(S30-A-Pad+)") (class "Default")
      (node (ref "S30") (pin "+") (pinfunction "A_+") (pintype "passive"))
    )
    (net (code "139") (name "unconnected-(S30-C-Pad-)") (class "Default")
      (node (ref "S30") (pin "-") (pinfunction "C_-") (pintype "passive"))
    )
    (net (code "140") (name "unconnected-(S30-P1-Pad2)") (class "Default")
      (node (ref "S30") (pin "2") (pinfunction "P1_2") (pintype "passive"))
    )
    (net (code "141") (name "unconnected-(S30-S1-Pad4)") (class "Default")
      (node (ref "S30") (pin "4") (pinfunction "S1_4") (pintype "passive"))
    )
    (net (code "142") (name "unconnected-(S31-A-Pad+)") (class "Default")
      (node (ref "S31") (pin "+") (pinfunction "A_+") (pintype "passive"))
    )
    (net (code "143") (name "unconnected-(S31-C-Pad-)") (class "Default")
      (node (ref "S31") (pin "-") (pinfunction "C_-") (pintype "passive"))
    )
    (net (code "144") (name "unconnected-(S31-P1-Pad2)") (class "Default")
      (node (ref "S31") (pin "2") (pinfunction "P1_2") (pintype "passive"))
    )
    (net (code "145") (name "unconnected-(S31-S1-Pad4)") (class "Default")
      (node (ref "S31") (pin "4") (pinfunction "S1_4") (pintype "passive"))
    )
    (net (code "146") (name "unconnected-(S32-A-Pad+)") (class "Default")
      (node (ref "S32") (pin "+") (pinfunction "A_+") (pintype "passive"))
    )
    (net (code "147") (name "unconnected-(S32-C-Pad-)") (class "Default")
      (node (ref "S32") (pin "-") (pinfunction "C_-") (pintype "passive"))
    )
    (net (code "148") (name "unconnected-(S32-P1-Pad2)") (class "Default")
      (node (ref "S32") (pin "2") (pinfunction "P1_2") (pintype "passive"))
    )
    (net (code "149") (name "unconnected-(S32-S1-Pad4)") (class "Default")
      (node (ref "S32") (pin "4") (pinfunction "S1_4") (pintype "passive"))
    )
    (net (code "150") (name "unconnected-(S33-A-Pad+)") (class "Default")
      (node (ref "S33") (pin "+") (pinfunction "A_+") (pintype "passive"))
    )
    (net (code "151") (name "unconnected-(S33-C-Pad-)") (class "Default")
      (node (ref "S33") (pin "-") (pinfunction "C_-") (pintype "passive"))
    )
    (net (code "152") (name "unconnected-(S33-P1-Pad2)") (class "Default")
      (node (ref "S33") (pin "2") (pinfunction "P1_2") (pintype "passive"))
    )
    (net (code "153") (name "unconnected-(S33-S1-Pad4)") (class "Default")
      (node (ref "S33") (pin "4") (pinfunction "S1_4") (pintype "passive"))
    )
    (net (code "154") (name "unconnected-(S34-A-Pad+)") (class "Default")
      (node (ref "S34") (pin "+") (pinfunction "A_+") (pintype "passive"))
    )
    (net (code "155") (name "unconnected-(S34-C-Pad-)") (class "Default")
      (node (ref "S34") (pin "-") (pinfunction "C_-") (pintype "passive"))
    )
    (net (code "156") (name "unconnected-(S34-P1-Pad2)") (class "Default")
      (node (ref "S34") (pin "2") (pinfunction "P1_2") (pintype "passive"))
    )
    (net (code "157") (name "unconnected-(S34-S1-Pad4)") (class "Default")
      (node (ref "S34") (pin "4") (pinfunction "S1_4") (pintype "passive"))
    )
    (net (code "158") (name "unconnected-(S35-A-Pad+)") (class "Default")
      (node (ref "S35") (pin "+") (pinfunction "A_+") (pintype "passive"))
    )
    (net (code "159") (name "unconnected-(S35-C-Pad-)") (class "Default")
      (node (ref "S35") (pin "-") (pinfunction "C_-") (pintype "passive"))
    )
    (net (code "160") (name "unconnected-(S35-P1-Pad2)") (class "Default")
      (node (ref "S35") (pin "2") (pinfunction "P1_2") (pintype "passive"))
    )
    (net (code "161") (name "unconnected-(S35-S-Pad3)") (class "Default")
      (node (ref "S35") (pin "3") (pinfunction "S_3") (pintype "passive"))
    )
    (net (code "162") (name "unconnected-(S35-S1-Pad4)") (class "Default")
      (node (ref "S35") (pin "4") (pinfunction "S1_4") (pintype "passive"))
    )
    (net (code "163") (name "unconnected-(S36-A-Pad+)") (class "Default")
      (node (ref "S36") (pin "+") (pinfunction "A_+") (pintype "passive"))
    )
    (net (code "164") (name "unconnected-(S36-C-Pad-)") (class "Default")
      (node (ref "S36") (pin "-") (pinfunction "C_-") (pintype "passive"))
    )
    (net (code "165") (name "unconnected-(S36-P1-Pad2)") (class "Default")
      (node (ref "S36") (pin "2") (pinfunction "P1_2") (pintype "passive"))
    )
    (net (code "166") (name "unconnected-(S36-S1-Pad4)") (class "Default")
      (node (ref "S36") (pin "4") (pinfunction "S1_4") (pintype "passive"))
    )
    (net (code "167") (name "unconnected-(S37-A-Pad+)") (class "Default")
      (node (ref "S37") (pin "+") (pinfunction "A_+") (pintype "passive"))
    )
    (net (code "168") (name "unconnected-(S37-C-Pad-)") (class "Default")
      (node (ref "S37") (pin "-") (pinfunction "C_-") (pintype "passive"))
    )
    (net (code "169") (name "unconnected-(S37-P1-Pad2)") (class "Default")
      (node (ref "S37") (pin "2") (pinfunction "P1_2") (pintype "passive"))
    )
    (net (code "170") (name "unconnected-(S37-S1-Pad4)") (class "Default")
      (node (ref "S37") (pin "4") (pinfunction "S1_4") (pintype "passive"))
    )
    (net (code "171") (name "unconnected-(S38-A-Pad+)") (class "Default")
      (node (ref "S38") (pin "+") (pinfunction "A_+") (pintype "passive"))
    )
    (net (code "172") (name "unconnected-(S38-C-Pad-)") (class "Default")
      (node (ref "S38") (pin "-") (pinfunction "C_-") (pintype "passive"))
    )
    (net (code "173") (name "unconnected-(S38-P1-Pad2)") (class "Default")
      (node (ref "S38") (pin "2") (pinfunction "P1_2") (pintype "passive"))
    )
    (net (code "174") (name "unconnected-(S38-S1-Pad4)") (class "Default")
      (node (ref "S38") (pin "4") (pinfunction "S1_4") (pintype "passive"))
    )
    (net (code "175") (name "unconnected-(S39-A-Pad+)") (class "Default")
      (node (ref "S39") (pin "+") (pinfunction "A_+") (pintype "passive"))
    )
    (net (code "176") (name "unconnected-(S39-C-Pad-)") (class "Default")
      (node (ref "S39") (pin "-") (pinfunction "C_-") (pintype "passive"))
    )
    (net (code "177") (name "unconnected-(S39-P1-Pad2)") (class "Default")
      (node (ref "S39") (pin "2") (pinfunction "P1_2") (pintype "passive"))
    )
    (net (code "178") (name "unconnected-(S39-S1-Pad4)") (class "Default")
      (node (ref "S39") (pin "4") (pinfunction "S1_4") (pintype "passive"))
    )
    (net (code "179") (name "unconnected-(S40-A-Pad+)") (class "Default")
      (node (ref "S40") (pin "+") (pinfunction "A_+") (pintype "passive"))
    )
    (net (code "180") (name "unconnected-(S40-C-Pad-)") (class "Default")
      (node (ref "S40") (pin "-") (pinfunction "C_-") (pintype "passive"))
    )
    (net (code "181") (name "unconnected-(S40-P1-Pad2)") (class "Default")
      (node (ref "S40") (pin "2") (pinfunction "P1_2") (pintype "passive"))
    )
    (net (code "182") (name "unconnected-(S40-S1-Pad4)") (class "Default")
      (node (ref "S40") (pin "4") (pinfunction "S1_4") (pintype "passive"))
    )
    (net (code "183") (name "unconnected-(S41-A-Pad+)") (class "Default")
      (node (ref "S41") (pin "+") (pinfunction "A_+") (pintype "passive"))
    )
    (net (code "184") (name "unconnected-(S41-C-Pad-)") (class "Default")
      (node (ref "S41") (pin "-") (pinfunction "C_-") (pintype "passive"))
    )
    (net (code "185") (name "unconnected-(S41-P1-Pad2)") (class "Default")
      (node (ref "S41") (pin "2") (pinfunction "P1_2") (pintype "passive"))
    )
    (net (code "186") (name "unconnected-(S41-S1-Pad4)") (class "Default")
      (node (ref "S41") (pin "4") (pinfunction "S1_4") (pintype "passive"))
    )
    (net (code "187") (name "unconnected-(S42-A-Pad+)") (class "Default")
      (node (ref "S42") (pin "+") (pinfunction "A_+") (pintype "passive"))
    )
    (net (code "188") (name "unconnected-(S42-C-Pad-)") (class "Default")
      (node (ref "S42") (pin "-") (pinfunction "C_-") (pintype "passive"))
    )
    (net (code "189") (name "unconnected-(S42-P1-Pad2)") (class "Default")
      (node (ref "S42") (pin "2") (pinfunction "P1_2") (pintype "passive"))
    )
    (net (code "190") (name "unconnected-(S42-S1-Pad4)") (class "Default")
      (node (ref "S42") (pin "4") (pinfunction "S1_4") (pintype "passive"))
    )
    (net (code "191") (name "unconnected-(S43-A-Pad+)") (class "Default")
      (node (ref "S43") (pin "+") (pinfunction "A_+") (pintype "passive"))
    )
    (net (code "192") (name "unconnected-(S43-C-Pad-)") (class "Default")
      (node (ref "S43") (pin "-") (pinfunction "C_-") (pintype "passive"))
    )
    (net (code "193") (name "unconnected-(S43-P1-Pad2)") (class "Default")
      (node (ref "S43") (pin "2") (pinfunction "P1_2") (pintype "passive"))
    )
    (net (code "194") (name "unconnected-(S43-S1-Pad4)") (class "Default")
      (node (ref "S43") (pin "4") (pinfunction "S1_4") (pintype "passive"))
    )
    (net (code "195") (name "unconnected-(S44-A-Pad+)") (class "Default")
      (node (ref "S44") (pin "+") (pinfunction "A_+") (pintype "passive"))
    )
    (net (code "196") (name "unconnected-(S44-C-Pad-)") (class "Default")
      (node (ref "S44") (pin "-") (pinfunction "C_-") (pintype "passive"))
    )
    (net (code "197") (name "unconnected-(S44-P1-Pad2)") (class "Default")
      (node (ref "S44") (pin "2") (pinfunction "P1_2") (pintype "passive"))
    )
    (net (code "198") (name "unconnected-(S44-S-Pad3)") (class "Default")
      (node (ref "S44") (pin "3") (pinfunction "S_3") (pintype "passive"))
    )
    (net (code "199") (name "unconnected-(S44-S1-Pad4)") (class "Default")
      (node (ref "S44") (pin "4") (pinfunction "S1_4") (pintype "passive"))
    )
    (net (code "200") (name "unconnected-(S45-A-Pad+)") (class "Default")
      (node (ref "S45") (pin "+") (pinfunction "A_+") (pintype "passive"))
    )
    (net (code "201") (name "unconnected-(S45-C-Pad-)") (class "Default")
      (node (ref "S45") (pin "-") (pinfunction "C_-") (pintype "passive"))
    )
    (net (code "202") (name "unconnected-(S45-P1-Pad2)") (class "Default")
      (node (ref "S45") (pin "2") (pinfunction "P1_2") (pintype "passive"))
    )
    (net (code "203") (name "unconnected-(S45-S1-Pad4)") (class "Default")
      (node (ref "S45") (pin "4") (pinfunction "S1_4") (pintype "passive"))
    )
    (net (code "204") (name "unconnected-(S46-A-Pad+)") (class "Default")
      (node (ref "S46") (pin "+") (pinfunction "A_+") (pintype "passive"))
    )
    (net (code "205") (name "unconnected-(S46-C-Pad-)") (class "Default")
      (node (ref "S46") (pin "-") (pinfunction "C_-") (pintype "passive"))
    )
    (net (code "206") (name "unconnected-(S46-P1-Pad2)") (class "Default")
      (node (ref "S46") (pin "2") (pinfunction "P1_2") (pintype "passive"))
    )
    (net (code "207") (name "unconnected-(S46-S1-Pad4)") (class "Default")
      (node (ref "S46") (pin "4") (pinfunction "S1_4") (pintype "passive"))
    )
    (net (code "208") (name "unconnected-(S47-A-Pad+)") (class "Default")
      (node (ref "S47") (pin "+") (pinfunction "A_+") (pintype "passive"))
    )
    (net (code "209") (name "unconnected-(S47-C-Pad-)") (class "Default")
      (node (ref "S47") (pin "-") (pinfunction "C_-") (pintype "passive"))
    )
    (net (code "210") (name "unconnected-(S47-P1-Pad2)") (class "Default")
      (node (ref "S47") (pin "2") (pinfunction "P1_2") (pintype "passive"))
    )
    (net (code "211") (name "unconnected-(S47-S1-Pad4)") (class "Default")
      (node (ref "S47") (pin "4") (pinfunction "S1_4") (pintype "passive"))
    )
    (net (code "212") (name "unconnected-(S48-A-Pad+)") (class "Default")
      (node (ref "S48") (pin "+") (pinfunction "A_+") (pintype "passive"))
    )
    (net (code "213") (name "unconnected-(S48-C-Pad-)") (class "Default")
      (node (ref "S48") (pin "-") (pinfunction "C_-") (pintype "passive"))
    )
    (net (code "214") (name "unconnected-(S48-P1-Pad2)") (class "Default")
      (node (ref "S48") (pin "2") (pinfunction "P1_2") (pintype "passive"))
    )
    (net (code "215") (name "unconnected-(S48-S1-Pad4)") (class "Default")
      (node (ref "S48") (pin "4") (pinfunction "S1_4") (pintype "passive"))
    )
    (net (code "216") (name "unconnected-(S49-A-Pad+)") (class "Default")
      (node (ref "S49") (pin "+") (pinfunction "A_+") (pintype "passive"))
    )
    (net (code "217") (name "unconnected-(S49-C-Pad-)") (class "Default")
      (node (ref "S49") (pin "-") (pinfunction "C_-") (pintype "passive"))
    )
    (net (code "218") (name "unconnected-(S49-P1-Pad2)") (class "Default")
      (node (ref "S49") (pin "2") (pinfunction "P1_2") (pintype "passive"))
    )
    (net (code "219") (name "unconnected-(S49-S1-Pad4)") (class "Default")
      (node (ref "S49") (pin "4") (pinfunction "S1_4") (pintype "passive"))
    )
    (net (code "220") (name "unconnected-(S50-A-Pad+)") (class "Default")
      (node (ref "S50") (pin "+") (pinfunction "A_+") (pintype "passive"))
    )
    (net (code "221") (name "unconnected-(S50-C-Pad-)") (class "Default")
      (node (ref "S50") (pin "-") (pinfunction "C_-") (pintype "passive"))
    )
    (net (code "222") (name "unconnected-(S50-P1-Pad2)") (class "Default")
      (node (ref "S50") (pin "2") (pinfunction "P1_2") (pintype "passive"))
    )
    (net (code "223") (name "unconnected-(S50-S1-Pad4)") (class "Default")
      (node (ref "S50") (pin "4") (pinfunction "S1_4") (pintype "passive"))
    )
    (net (code "224") (name "unconnected-(S51-A-Pad+)") (class "Default")
      (node (ref "S51") (pin "+") (pinfunction "A_+") (pintype "passive"))
    )
    (net (code "225") (name "unconnected-(S51-C-Pad-)") (class "Default")
      (node (ref "S51") (pin "-") (pinfunction "C_-") (pintype "passive"))
    )
    (net (code "226") (name "unconnected-(S51-P1-Pad2)") (class "Default")
      (node (ref "S51") (pin "2") (pinfunction "P1_2") (pintype "passive"))
    )
    (net (code "227") (name "unconnected-(S51-S1-Pad4)") (class "Default")
      (node (ref "S51") (pin "4") (pinfunction "S1_4") (pintype "passive"))
    )
    (net (code "228") (name "unconnected-(S52-A-Pad+)") (class "Default")
      (node (ref "S52") (pin "+") (pinfunction "A_+") (pintype "passive"))
    )
    (net (code "229") (name "unconnected-(S52-C-Pad-)") (class "Default")
      (node (ref "S52") (pin "-") (pinfunction "C_-") (pintype "passive"))
    )
    (net (code "230") (name "unconnected-(S52-P1-Pad2)") (class "Default")
      (node (ref "S52") (pin "2") (pinfunction "P1_2") (pintype "passive"))
    )
    (net (code "231") (name "unconnected-(S52-S1-Pad4)") (class "Default")
      (node (ref "S52") (pin "4") (pinfunction "S1_4") (pintype "passive"))
    )
    (net (code "232") (name "unconnected-(S53-A-Pad+)") (class "Default")
      (node (ref "S53") (pin "+") (pinfunction "A_+") (pintype "passive"))
    )
    (net (code "233") (name "unconnected-(S53-C-Pad-)") (class "Default")
      (node (ref "S53") (pin "-") (pinfunction "C_-") (pintype "passive"))
    )
    (net (code "234") (name "unconnected-(S53-P1-Pad2)") (class "Default")
      (node (ref "S53") (pin "2") (pinfunction "P1_2") (pintype "passive"))
    )
    (net (code "235") (name "unconnected-(S53-S1-Pad4)") (class "Default")
      (node (ref "S53") (pin "4") (pinfunction "S1_4") (pintype "passive"))
    )
    (net (code "236") (name "unconnected-(S54-A-Pad+)") (class "Default")
      (node (ref "S54") (pin "+") (pinfunction "A_+") (pintype "passive"))
    )
    (net (code "237") (name "unconnected-(S54-C-Pad-)") (class "Default")
      (node (ref "S54") (pin "-") (pinfunction "C_-") (pintype "passive"))
    )
    (net (code "238") (name "unconnected-(S54-P1-Pad2)") (class "Default")
      (node (ref "S54") (pin "2") (pinfunction "P1_2") (pintype "passive"))
    )
    (net (code "239") (name "unconnected-(S54-S1-Pad4)") (class "Default")
      (node (ref "S54") (pin "4") (pinfunction "S1_4") (pintype "passive"))
    )
    (net (code "240") (name "unconnected-(S55-A-Pad+)") (class "Default")
      (node (ref "S55") (pin "+") (pinfunction "A_+") (pintype "passive"))
    )
    (net (code "241") (name "unconnected-(S55-C-Pad-)") (class "Default")
      (node (ref "S55") (pin "-") (pinfunction "C_-") (pintype "passive"))
    )
    (net (code "242") (name "unconnected-(S55-P1-Pad2)") (class "Default")
      (node (ref "S55") (pin "2") (pinfunction "P1_2") (pintype "passive"))
    )
    (net (code "243") (name "unconnected-(S55-S1-Pad4)") (class "Default")
      (node (ref "S55") (pin "4") (pinfunction "S1_4") (pintype "passive"))
    )
    (net (code "244") (name "unconnected-(S56-A-Pad+)") (class "Default")
      (node (ref "S56") (pin "+") (pinfunction "A_+") (pintype "passive"))
    )
    (net (code "245") (name "unconnected-(S56-C-Pad-)") (class "Default")
      (node (ref "S56") (pin "-") (pinfunction "C_-") (pintype "passive"))
    )
    (net (code "246") (name "unconnected-(S56-P1-Pad2)") (class "Default")
      (node (ref "S56") (pin "2") (pinfunction "P1_2") (pintype "passive"))
    )
    (net (code "247") (name "unconnected-(S56-S1-Pad4)") (class "Default")
      (node (ref "S56") (pin "4") (pinfunction "S1_4") (pintype "passive"))
    )
    (net (code "248") (name "unconnected-(S57-A-Pad+)") (class "Default")
      (node (ref "S57") (pin "+") (pinfunction "A_+") (pintype "passive"))
    )
    (net (code "249") (name "unconnected-(S57-C-Pad-)") (class "Default")
      (node (ref "S57") (pin "-") (pinfunction "C_-") (pintype "passive"))
    )
    (net (code "250") (name "unconnected-(S57-P1-Pad2)") (class "Default")
      (node (ref "S57") (pin "2") (pinfunction "P1_2") (pintype "passive"))
    )
    (net (code "251") (name "unconnected-(S57-S1-Pad4)") (class "Default")
      (node (ref "S57") (pin "4") (pinfunction "S1_4") (pintype "passive"))
    )
    (net (code "252") (name "unconnected-(S64-A-Pad+)") (class "Default")
      (node (ref "S64") (pin "+") (pinfunction "A_+") (pintype "passive"))
    )
    (net (code "253") (name "unconnected-(S64-C-Pad-)") (class "Default")
      (node (ref "S64") (pin "-") (pinfunction "C_-") (pintype "passive"))
    )
    (net (code "254") (name "unconnected-(S64-P1-Pad2)") (class "Default")
      (node (ref "S64") (pin "2") (pinfunction "P1_2") (pintype "passive"))
    )
    (net (code "255") (name "unconnected-(S64-S1-Pad4)") (class "Default")
      (node (ref "S64") (pin "4") (pinfunction "S1_4") (pintype "passive"))
    )
    (net (code "256") (name "unconnected-(S65-A-Pad+)") (class "Default")
      (node (ref "S65") (pin "+") (pinfunction "A_+") (pintype "passive"))
    )
    (net (code "257") (name "unconnected-(S65-C-Pad-)") (class "Default")
      (node (ref "S65") (pin "-") (pinfunction "C_-") (pintype "passive"))
    )
    (net (code "258") (name "unconnected-(S65-P1-Pad2)") (class "Default")
      (node (ref "S65") (pin "2") (pinfunction "P1_2") (pintype "passive"))
    )
    (net (code "259") (name "unconnected-(S65-S1-Pad4)") (class "Default")
      (node (ref "S65") (pin "4") (pinfunction "S1_4") (pintype "passive"))
    )
    (net (code "260") (name "unconnected-(S66-A-Pad+)") (class "Default")
      (node (ref "S66") (pin "+") (pinfunction "A_+") (pintype "passive"))
    )
    (net (code "261") (name "unconnected-(S66-C-Pad-)") (class "Default")
      (node (ref "S66") (pin "-") (pinfunction "C_-") (pintype "passive"))
    )
    (net (code "262") (name "unconnected-(S66-P1-Pad2)") (class "Default")
      (node (ref "S66") (pin "2") (pinfunction "P1_2") (pintype "passive"))
    )
    (net (code "263") (name "unconnected-(S66-S1-Pad4)") (class "Default")
      (node (ref "S66") (pin "4") (pinfunction "S1_4") (pintype "passive"))
    )
    (net (code "264") (name "unconnected-(S73-A-Pad+)") (class "Default")
      (node (ref "S73") (pin "+") (pinfunction "A_+") (pintype "passive"))
    )
    (net (code "265") (name "unconnected-(S73-C-Pad-)") (class "Default")
      (node (ref "S73") (pin "-") (pinfunction "C_-") (pintype "passive"))
    )
    (net (code "266") (name "unconnected-(S73-P1-Pad2)") (class "Default")
      (node (ref "S73") (pin "2") (pinfunction "P1_2") (pintype "passive"))
    )
    (net (code "267") (name "unconnected-(S73-S1-Pad4)") (class "Default")
      (node (ref "S73") (pin "4") (pinfunction "S1_4") (pintype "passive"))
    )
    (net (code "268") (name "unconnected-(S74-A-Pad+)") (class "Default")
      (node (ref "S74") (pin "+") (pinfunction "A_+") (pintype "passive"))
    )
    (net (code "269") (name "unconnected-(S74-C-Pad-)") (class "Default")
      (node (ref "S74") (pin "-") (pinfunction "C_-") (pintype "passive"))
    )
    (net (code "270") (name "unconnected-(S74-P1-Pad2)") (class "Default")
      (node (ref "S74") (pin "2") (pinfunction "P1_2") (pintype "passive"))
    )
    (net (code "271") (name "unconnected-(S74-S1-Pad4)") (class "Default")
      (node (ref "S74") (pin "4") (pinfunction "S1_4") (pintype "passive"))
    )
  )
)
